# SatNOGSBoard_UNO.net
KiCad netlist of a schematic drawn in EAGLE
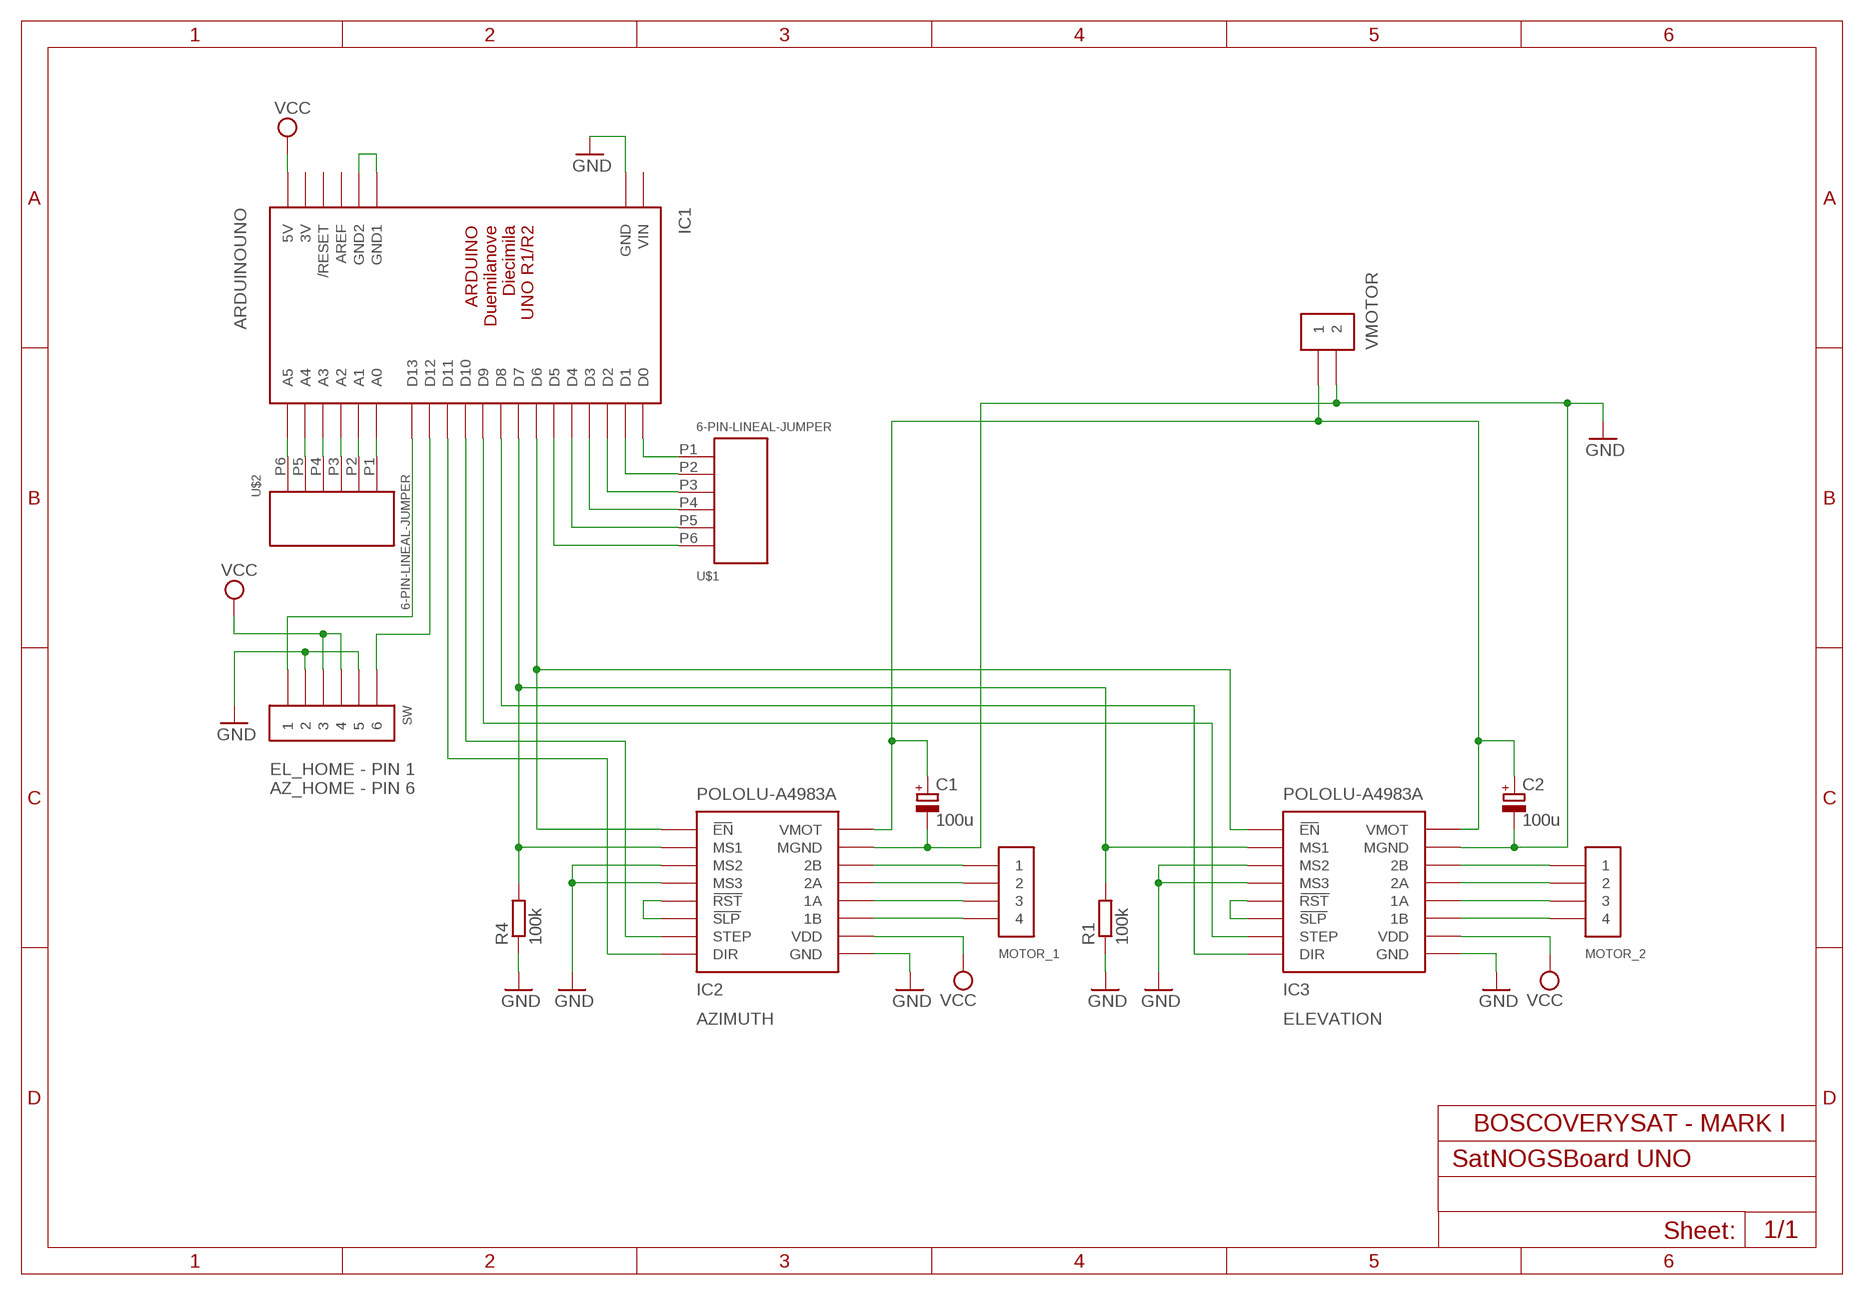
[diagram p0: schematic, sheet 1]

(export (version "E")
  (design (tool "Eeschema 10.0.6"))
  (components
    (comp (ref "C1")
      (value "100u")
      (footprint "eagle-import:B45181B")
      (libsource (lib "eagle-import") (part "CPOL-EUB45181B"))
    )
    (comp (ref "C2")
      (value "100u")
      (footprint "eagle-import:B45181B")
      (libsource (lib "eagle-import") (part "CPOL-EUB45181B"))
    )
    (comp (ref "IC1")
      (value "ARDUINOUNO")
      (footprint "eagle-import:ARDUINO")
      (libsource (lib "eagle-import") (part "ARDUINOUNO"))
    )
    (comp (ref "IC2")
      (value "POLOLU-A4983A")
      (footprint "eagle-import:POLOLU-A4983")
      (libsource (lib "eagle-import") (part "POLOLU-A4983A"))
    )
    (comp (ref "IC3")
      (value "POLOLU-A4983A")
      (footprint "eagle-import:POLOLU-A4983")
      (libsource (lib "eagle-import") (part "POLOLU-A4983A"))
    )
    (comp (ref "MOTOR_1")
      (value "4-WIRE-CONNECTOR")
      (footprint "eagle-import:4-WIRE-CONNECTOR")
      (libsource (lib "eagle-import") (part "4-WIRE-CONNECTOR"))
    )
    (comp (ref "MOTOR_2")
      (value "4-WIRE-CONNECTOR")
      (footprint "eagle-import:4-WIRE-CONNECTOR")
      (libsource (lib "eagle-import") (part "4-WIRE-CONNECTOR"))
    )
    (comp (ref "R1")
      (value "100k")
      (footprint "eagle-import:0309_10")
      (libsource (lib "eagle-import") (part "R-EU_0309/10"))
    )
    (comp (ref "R4")
      (value "100k")
      (footprint "eagle-import:0309_10")
      (libsource (lib "eagle-import") (part "R-EU_0309/10"))
    )
    (comp (ref "SW")
      (value "6-PIN-JUMPER")
      (footprint "eagle-import:6-PIN-JUMPER")
      (libsource (lib "eagle-import") (part "6-PIN-JUMPER"))
    )
    (comp (ref "U$1")
      (value "6-PIN-LINEAL-JUMPER")
      (footprint "eagle-import:6-PIN-LINEAR-JUMPER")
      (libsource (lib "eagle-import") (part "6-PIN-LINEAL-JUMPER"))
    )
    (comp (ref "U$2")
      (value "6-PIN-LINEAL-JUMPER")
      (footprint "eagle-import:6-PIN-LINEAR-JUMPER")
      (libsource (lib "eagle-import") (part "6-PIN-LINEAL-JUMPER"))
    )
    (comp (ref "VMOTOR")
      (value "2-WIRE-CONNECTOR")
      (footprint "eagle-import:2-WIRE-CONNECTOR")
      (libsource (lib "eagle-import") (part "2-WIRE-CONNECTOR"))
    )
  )
  (nets
    (net (code "1") (name "/3V") (class "Default")
      (node (ref "IC1") (pin "3V") (pinfunction "3V_3V") (pintype "power_in"))
    )
    (net (code "2") (name "/VIN") (class "Default")
      (node (ref "IC1") (pin "VIN") (pinfunction "VIN_VIN") (pintype "power_in"))
    )
    (net (code "3") (name "GND") (class "Default")
      (node (ref "C1") (pin "-") (pinfunction "-_-") (pintype "passive"))
      (node (ref "C2") (pin "-") (pinfunction "-_-") (pintype "passive"))
      (node (ref "IC1") (pin "GND") (pinfunction "GND_GND") (pintype "power_in"))
      (node (ref "IC2") (pin "P$15") (pinfunction "MGND_P$15") (pintype "bidirectional"))
      (node (ref "IC2") (pin "P$3") (pinfunction "MS2_P$3") (pintype "bidirectional"))
      (node (ref "IC2") (pin "P$4") (pinfunction "MS3_P$4") (pintype "bidirectional"))
      (node (ref "IC2") (pin "P$9") (pinfunction "GND_P$9") (pintype "bidirectional"))
      (node (ref "IC3") (pin "P$15") (pinfunction "MGND_P$15") (pintype "bidirectional"))
      (node (ref "IC3") (pin "P$3") (pinfunction "MS2_P$3") (pintype "bidirectional"))
      (node (ref "IC3") (pin "P$4") (pinfunction "MS3_P$4") (pintype "bidirectional"))
      (node (ref "IC3") (pin "P$9") (pinfunction "GND_P$9") (pintype "bidirectional"))
      (node (ref "R1") (pin "1") (pinfunction "1_1") (pintype "passive"))
      (node (ref "R4") (pin "1") (pinfunction "1_1") (pintype "passive"))
      (node (ref "SW") (pin "P$2") (pinfunction "2_P$2") (pintype "bidirectional"))
      (node (ref "SW") (pin "P$5") (pinfunction "5_P$5") (pintype "bidirectional"))
      (node (ref "VMOTOR") (pin "P$2") (pinfunction "2_P$2") (pintype "bidirectional"))
    )
    (net (code "4") (name "Net-(IC1-PadGND1)") (class "Default")
      (node (ref "IC1") (pin "GND1") (pinfunction "GND1_GND1") (pintype "bidirectional"))
      (node (ref "IC1") (pin "GND2") (pinfunction "GND2_GND2") (pintype "bidirectional"))
    )
    (net (code "5") (name "Net-(IC2-1A)") (class "Default")
      (node (ref "IC2") (pin "P$12") (pinfunction "1A_P$12") (pintype "bidirectional"))
      (node (ref "MOTOR_1") (pin "P$3") (pinfunction "3_P$3") (pintype "bidirectional"))
    )
    (net (code "6") (name "Net-(IC2-1B)") (class "Default")
      (node (ref "IC2") (pin "P$11") (pinfunction "1B_P$11") (pintype "bidirectional"))
      (node (ref "MOTOR_1") (pin "P$4") (pinfunction "4_P$4") (pintype "bidirectional"))
    )
    (net (code "7") (name "Net-(IC2-2A)") (class "Default")
      (node (ref "IC2") (pin "P$13") (pinfunction "2A_P$13") (pintype "bidirectional"))
      (node (ref "MOTOR_1") (pin "P$2") (pinfunction "2_P$2") (pintype "bidirectional"))
    )
    (net (code "8") (name "Net-(IC2-2B)") (class "Default")
      (node (ref "IC2") (pin "P$14") (pinfunction "2B_P$14") (pintype "bidirectional"))
      (node (ref "MOTOR_1") (pin "P$1") (pinfunction "1_P$1") (pintype "bidirectional"))
    )
    (net (code "9") (name "Net-(IC2-DIR)") (class "Default")
      (node (ref "IC1") (pin "D11") (pinfunction "D11_D11") (pintype "bidirectional"))
      (node (ref "IC2") (pin "P$8") (pinfunction "DIR_P$8") (pintype "bidirectional"))
    )
    (net (code "10") (name "Net-(IC2-EN)") (class "Default")
      (node (ref "IC1") (pin "D6") (pinfunction "D6_D6") (pintype "bidirectional"))
      (node (ref "IC2") (pin "P$1") (pinfunction "EN_P$1") (pintype "bidirectional"))
      (node (ref "IC3") (pin "P$1") (pinfunction "EN_P$1") (pintype "bidirectional"))
    )
    (net (code "11") (name "Net-(IC2-MS1)") (class "Default")
      (node (ref "IC1") (pin "D7") (pinfunction "D7_D7") (pintype "bidirectional"))
      (node (ref "IC2") (pin "P$2") (pinfunction "MS1_P$2") (pintype "bidirectional"))
      (node (ref "IC3") (pin "P$2") (pinfunction "MS1_P$2") (pintype "bidirectional"))
      (node (ref "R1") (pin "2") (pinfunction "2_2") (pintype "passive"))
      (node (ref "R4") (pin "2") (pinfunction "2_2") (pintype "passive"))
    )
    (net (code "12") (name "Net-(IC2-RST)") (class "Default")
      (node (ref "IC2") (pin "P$5") (pinfunction "RST_P$5") (pintype "bidirectional"))
      (node (ref "IC2") (pin "P$6") (pinfunction "SLP_P$6") (pintype "bidirectional"))
    )
    (net (code "13") (name "Net-(IC2-STEP)") (class "Default")
      (node (ref "IC1") (pin "D10") (pinfunction "D10_D10") (pintype "bidirectional"))
      (node (ref "IC2") (pin "P$7") (pinfunction "STEP_P$7") (pintype "bidirectional"))
    )
    (net (code "14") (name "Net-(IC2-VMOT)") (class "Default")
      (node (ref "C1") (pin "+") (pinfunction "+_+") (pintype "passive"))
      (node (ref "C2") (pin "+") (pinfunction "+_+") (pintype "passive"))
      (node (ref "IC2") (pin "P$16") (pinfunction "VMOT_P$16") (pintype "bidirectional"))
      (node (ref "IC3") (pin "P$16") (pinfunction "VMOT_P$16") (pintype "bidirectional"))
      (node (ref "VMOTOR") (pin "P$1") (pinfunction "1_P$1") (pintype "bidirectional"))
    )
    (net (code "15") (name "Net-(IC3-1A)") (class "Default")
      (node (ref "IC3") (pin "P$12") (pinfunction "1A_P$12") (pintype "bidirectional"))
      (node (ref "MOTOR_2") (pin "P$3") (pinfunction "3_P$3") (pintype "bidirectional"))
    )
    (net (code "16") (name "Net-(IC3-1B)") (class "Default")
      (node (ref "IC3") (pin "P$11") (pinfunction "1B_P$11") (pintype "bidirectional"))
      (node (ref "MOTOR_2") (pin "P$4") (pinfunction "4_P$4") (pintype "bidirectional"))
    )
    (net (code "17") (name "Net-(IC3-2A)") (class "Default")
      (node (ref "IC3") (pin "P$13") (pinfunction "2A_P$13") (pintype "bidirectional"))
      (node (ref "MOTOR_2") (pin "P$2") (pinfunction "2_P$2") (pintype "bidirectional"))
    )
    (net (code "18") (name "Net-(IC3-2B)") (class "Default")
      (node (ref "IC3") (pin "P$14") (pinfunction "2B_P$14") (pintype "bidirectional"))
      (node (ref "MOTOR_2") (pin "P$1") (pinfunction "1_P$1") (pintype "bidirectional"))
    )
    (net (code "19") (name "Net-(IC3-DIR)") (class "Default")
      (node (ref "IC1") (pin "D8") (pinfunction "D8_D8") (pintype "bidirectional"))
      (node (ref "IC3") (pin "P$8") (pinfunction "DIR_P$8") (pintype "bidirectional"))
    )
    (net (code "20") (name "Net-(IC3-RST)") (class "Default")
      (node (ref "IC3") (pin "P$5") (pinfunction "RST_P$5") (pintype "bidirectional"))
      (node (ref "IC3") (pin "P$6") (pinfunction "SLP_P$6") (pintype "bidirectional"))
    )
    (net (code "21") (name "Net-(IC3-STEP)") (class "Default")
      (node (ref "IC1") (pin "D9") (pinfunction "D9_D9") (pintype "bidirectional"))
      (node (ref "IC3") (pin "P$7") (pinfunction "STEP_P$7") (pintype "bidirectional"))
    )
    (net (code "22") (name "Net-(SW-1)") (class "Default")
      (node (ref "IC1") (pin "D13") (pinfunction "D13_D13") (pintype "bidirectional"))
      (node (ref "SW") (pin "P$1") (pinfunction "1_P$1") (pintype "bidirectional"))
    )
    (net (code "23") (name "Net-(SW-6)") (class "Default")
      (node (ref "IC1") (pin "D12") (pinfunction "D12_D12") (pintype "bidirectional"))
      (node (ref "SW") (pin "P$6") (pinfunction "6_P$6") (pintype "bidirectional"))
    )
    (net (code "24") (name "Net-(U$1-P$1)") (class "Default")
      (node (ref "IC1") (pin "D0") (pinfunction "D0_D0") (pintype "bidirectional"))
      (node (ref "U$1") (pin "P1") (pinfunction "P$1_P1") (pintype "bidirectional"))
    )
    (net (code "25") (name "Net-(U$1-P$2)") (class "Default")
      (node (ref "IC1") (pin "D1") (pinfunction "D1_D1") (pintype "bidirectional"))
      (node (ref "U$1") (pin "P2") (pinfunction "P$2_P2") (pintype "bidirectional"))
    )
    (net (code "26") (name "Net-(U$1-P$3)") (class "Default")
      (node (ref "IC1") (pin "D2") (pinfunction "D2_D2") (pintype "bidirectional"))
      (node (ref "U$1") (pin "P3") (pinfunction "P$3_P3") (pintype "bidirectional"))
    )
    (net (code "27") (name "Net-(U$1-P$4)") (class "Default")
      (node (ref "IC1") (pin "D3") (pinfunction "D3_D3") (pintype "bidirectional"))
      (node (ref "U$1") (pin "P4") (pinfunction "P$4_P4") (pintype "bidirectional"))
    )
    (net (code "28") (name "Net-(U$1-P$5)") (class "Default")
      (node (ref "IC1") (pin "D4") (pinfunction "D4_D4") (pintype "bidirectional"))
      (node (ref "U$1") (pin "P5") (pinfunction "P$5_P5") (pintype "bidirectional"))
    )
    (net (code "29") (name "Net-(U$1-P$6)") (class "Default")
      (node (ref "IC1") (pin "D5") (pinfunction "D5_D5") (pintype "bidirectional"))
      (node (ref "U$1") (pin "P6") (pinfunction "P$6_P6") (pintype "bidirectional"))
    )
    (net (code "30") (name "Net-(U$2-P$1)") (class "Default")
      (node (ref "IC1") (pin "A0") (pinfunction "A0_A0") (pintype "bidirectional"))
      (node (ref "U$2") (pin "P1") (pinfunction "P$1_P1") (pintype "bidirectional"))
    )
    (net (code "31") (name "Net-(U$2-P$2)") (class "Default")
      (node (ref "IC1") (pin "A1") (pinfunction "A1_A1") (pintype "bidirectional"))
      (node (ref "U$2") (pin "P2") (pinfunction "P$2_P2") (pintype "bidirectional"))
    )
    (net (code "32") (name "Net-(U$2-P$3)") (class "Default")
      (node (ref "IC1") (pin "A2") (pinfunction "A2_A2") (pintype "bidirectional"))
      (node (ref "U$2") (pin "P3") (pinfunction "P$3_P3") (pintype "bidirectional"))
    )
    (net (code "33") (name "Net-(U$2-P$4)") (class "Default")
      (node (ref "IC1") (pin "A3") (pinfunction "A3_A3") (pintype "bidirectional"))
      (node (ref "U$2") (pin "P4") (pinfunction "P$4_P4") (pintype "bidirectional"))
    )
    (net (code "34") (name "Net-(U$2-P$5)") (class "Default")
      (node (ref "IC1") (pin "A4") (pinfunction "A4_A4") (pintype "bidirectional"))
      (node (ref "U$2") (pin "P5") (pinfunction "P$5_P5") (pintype "bidirectional"))
    )
    (net (code "35") (name "Net-(U$2-P$6)") (class "Default")
      (node (ref "IC1") (pin "A5") (pinfunction "A5_A5") (pintype "bidirectional"))
      (node (ref "U$2") (pin "P6") (pinfunction "P$6_P6") (pintype "bidirectional"))
    )
    (net (code "36") (name "VCC") (class "Default")
      (node (ref "IC1") (pin "5V") (pinfunction "5V_5V") (pintype "power_in"))
      (node (ref "IC2") (pin "P$10") (pinfunction "VDD_P$10") (pintype "bidirectional"))
      (node (ref "IC3") (pin "P$10") (pinfunction "VDD_P$10") (pintype "bidirectional"))
      (node (ref "SW") (pin "P$3") (pinfunction "3_P$3") (pintype "bidirectional"))
      (node (ref "SW") (pin "P$4") (pinfunction "4_P$4") (pintype "bidirectional"))
    )
    (net (code "37") (name "unconnected-(IC1-PadAREF)") (class "Default")
      (node (ref "IC1") (pin "AREF") (pinfunction "AREF_AREF") (pintype "bidirectional"))
    )
    (net (code "38") (name "unconnected-(IC1-{slash}RESET-PadRESET)") (class "Default")
      (node (ref "IC1") (pin "RESET") (pinfunction "/RESET_RESET") (pintype "bidirectional"))
    )
  )
)
